# nv-h5b.net
KiCad netlist of a schematic drawn in EAGLE
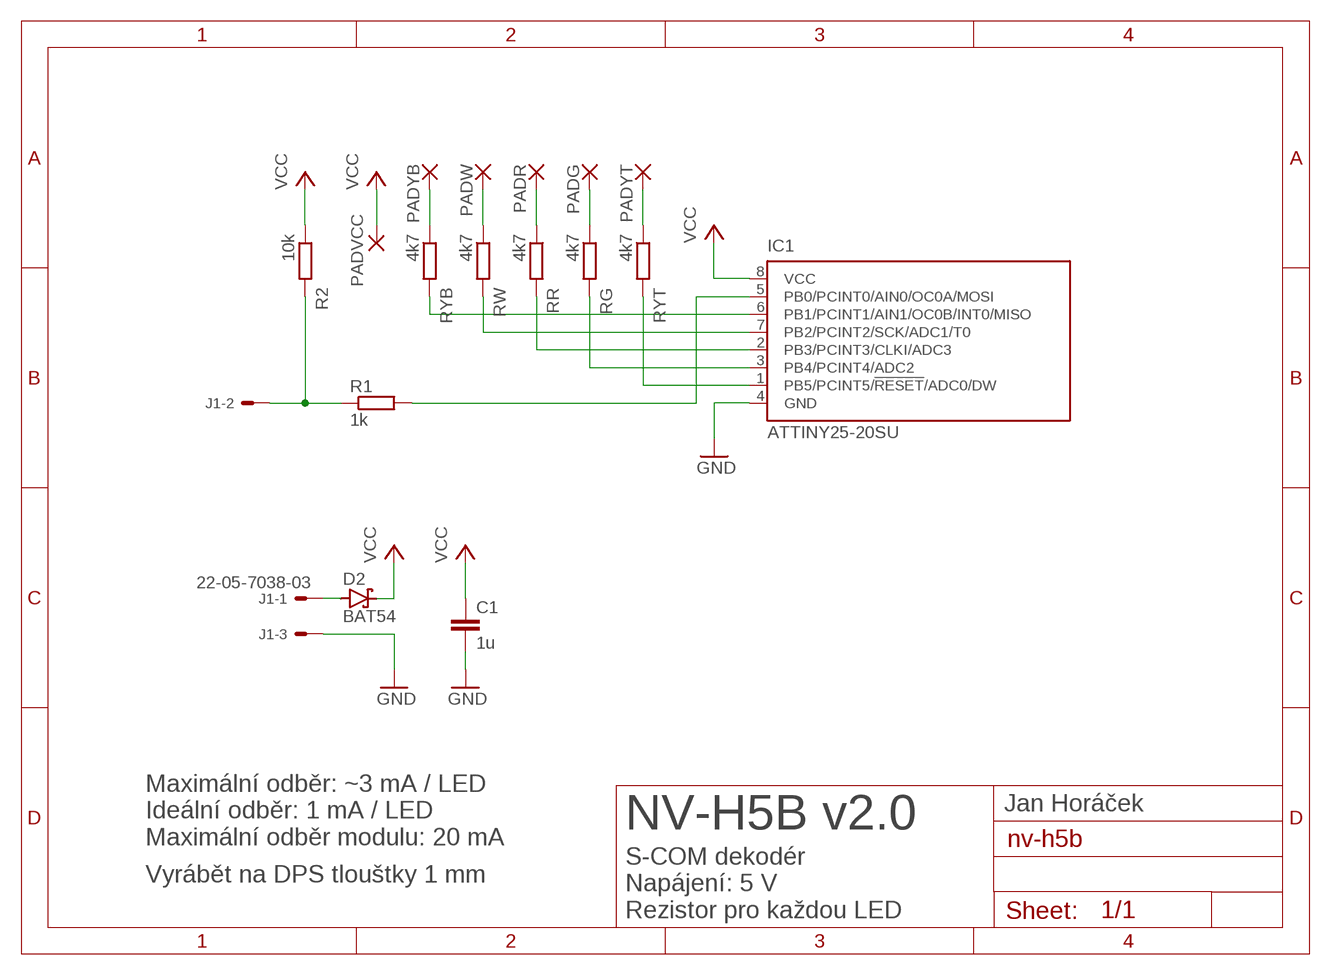
[diagram p0: schematic, sheet 1]

(export (version "E")
  (design (tool "Eeschema 10.0.6"))
  (components
    (comp (ref "C1")
      (value "1u")
      (footprint "eagle-import:C0805")
      (libsource (lib "eagle-import") (part "C-EUC0805"))
    )
    (comp (ref "D2")
      (value "BAT54")
      (footprint "eagle-import:SOT23")
      (libsource (lib "eagle-import") (part "BAT54"))
    )
    (comp (ref "IC1")
      (value "ATTINY25-20SU")
      (footprint "eagle-import:8S1")
      (fields (field (name "MPN") "ATTINY13-20SSU"))
      (libsource (lib "eagle-import") (part "TINY13SSU-20"))
    )
    (comp (ref "J1")
      (value "22-05-7038-03")
      (footprint "eagle-import:7395-03")
      (fields (field (name "MF") "MOLEX"))
      (libsource (lib "eagle-import") (part "22-?-0305-7038"))
    )
    (comp (ref "PADG")
      (value "SMD3")
      (footprint "eagle-import:SMD1,778-5,08")
      (libsource (lib "eagle-import") (part "SMD3"))
    )
    (comp (ref "PADR")
      (value "SMD3")
      (footprint "eagle-import:SMD1,778-5,08")
      (libsource (lib "eagle-import") (part "SMD3"))
    )
    (comp (ref "PADVCC")
      (value "SMD3")
      (footprint "eagle-import:SMD1,778-5,08")
      (libsource (lib "eagle-import") (part "SMD3"))
    )
    (comp (ref "PADW")
      (value "SMD3")
      (footprint "eagle-import:SMD1,778-5,08")
      (libsource (lib "eagle-import") (part "SMD3"))
    )
    (comp (ref "PADYB")
      (value "SMD3")
      (footprint "eagle-import:SMD1,778-5,08")
      (libsource (lib "eagle-import") (part "SMD3"))
    )
    (comp (ref "PADYT")
      (value "SMD3")
      (footprint "eagle-import:SMD1,778-5,08")
      (libsource (lib "eagle-import") (part "SMD3"))
    )
    (comp (ref "R1")
      (value "1k")
      (footprint "eagle-import:R0805")
      (libsource (lib "eagle-import") (part "R-EU_R0805"))
    )
    (comp (ref "R2")
      (value "10k")
      (footprint "eagle-import:R0805")
      (libsource (lib "eagle-import") (part "R-EU_R0805"))
    )
    (comp (ref "RG")
      (value "4k7")
      (footprint "eagle-import:R0805")
      (libsource (lib "eagle-import") (part "R-EU_R0805"))
    )
    (comp (ref "RR")
      (value "4k7")
      (footprint "eagle-import:R0805")
      (libsource (lib "eagle-import") (part "R-EU_R0805"))
    )
    (comp (ref "RW")
      (value "4k7")
      (footprint "eagle-import:R0805")
      (libsource (lib "eagle-import") (part "R-EU_R0805"))
    )
    (comp (ref "RYB")
      (value "4k7")
      (footprint "eagle-import:R0805")
      (libsource (lib "eagle-import") (part "R-EU_R0805"))
    )
    (comp (ref "RYT")
      (value "4k7")
      (footprint "eagle-import:R0805")
      (libsource (lib "eagle-import") (part "R-EU_R0805"))
    )
  )
  (nets
    (net (code "1") (name "GND") (class "Default")
      (node (ref "C1") (pin "2") (pinfunction "2_2") (pintype "passive"))
      (node (ref "IC1") (pin "4") (pinfunction "GND_4") (pintype "power_in"))
      (node (ref "J1") (pin "3") (pinfunction "S_3") (pintype "passive"))
    )
    (net (code "2") (name "Net-(D2-A)") (class "Default")
      (node (ref "D2") (pin "1") (pinfunction "A_1") (pintype "passive"))
      (node (ref "J1") (pin "1") (pinfunction "S_1") (pintype "passive"))
    )
    (net (code "3") (name "Net-(IC1-PB0{slash}PCINT0{slash}AIN0{slash}OC0A{slash}MOSI)") (class "Default")
      (node (ref "IC1") (pin "5") (pinfunction "PB0/PCINT0/AIN0/OC0A/MOSI_5") (pintype "bidirectional"))
      (node (ref "R1") (pin "2") (pinfunction "2_2") (pintype "passive"))
    )
    (net (code "4") (name "Net-(IC1-PB1{slash}PCINT1{slash}AIN1{slash}OC0B{slash}INT0{slash}MISO)") (class "Default")
      (node (ref "IC1") (pin "6") (pinfunction "PB1/PCINT1/AIN1/OC0B/INT0/MISO_6") (pintype "bidirectional"))
      (node (ref "RYB") (pin "2") (pinfunction "2_2") (pintype "passive"))
    )
    (net (code "5") (name "Net-(IC1-PB2{slash}PCINT2{slash}SCK{slash}ADC1{slash}T0)") (class "Default")
      (node (ref "IC1") (pin "7") (pinfunction "PB2/PCINT2/SCK/ADC1/T0_7") (pintype "bidirectional"))
      (node (ref "RW") (pin "2") (pinfunction "2_2") (pintype "passive"))
    )
    (net (code "6") (name "Net-(IC1-PB3{slash}PCINT3{slash}CLKI{slash}ADC3)") (class "Default")
      (node (ref "IC1") (pin "2") (pinfunction "PB3/PCINT3/CLKI/ADC3_2") (pintype "bidirectional"))
      (node (ref "RR") (pin "2") (pinfunction "2_2") (pintype "passive"))
    )
    (net (code "7") (name "Net-(IC1-PB4{slash}PCINT4{slash}ADC2)") (class "Default")
      (node (ref "IC1") (pin "3") (pinfunction "PB4/PCINT4/ADC2_3") (pintype "bidirectional"))
      (node (ref "RG") (pin "2") (pinfunction "2_2") (pintype "passive"))
    )
    (net (code "8") (name "Net-(IC1-PB5{slash}PCINT5{slash}~{RESET}{slash}ADC0{slash}DW)") (class "Default")
      (node (ref "IC1") (pin "1") (pinfunction "PB5/PCINT5/~{RESET}/ADC0/DW_1") (pintype "bidirectional"))
      (node (ref "RYT") (pin "2") (pinfunction "2_2") (pintype "passive"))
    )
    (net (code "9") (name "Net-(J1B-S)") (class "Default")
      (node (ref "J1") (pin "2") (pinfunction "S_2") (pintype "passive"))
      (node (ref "R1") (pin "1") (pinfunction "1_1") (pintype "passive"))
      (node (ref "R2") (pin "2") (pinfunction "2_2") (pintype "passive"))
    )
    (net (code "10") (name "Net-(PADG-P)") (class "Default")
      (node (ref "PADG") (pin "1") (pinfunction "P_1") (pintype "passive"))
      (node (ref "RG") (pin "1") (pinfunction "1_1") (pintype "passive"))
    )
    (net (code "11") (name "Net-(PADR-P)") (class "Default")
      (node (ref "PADR") (pin "1") (pinfunction "P_1") (pintype "passive"))
      (node (ref "RR") (pin "1") (pinfunction "1_1") (pintype "passive"))
    )
    (net (code "12") (name "Net-(PADW-P)") (class "Default")
      (node (ref "PADW") (pin "1") (pinfunction "P_1") (pintype "passive"))
      (node (ref "RW") (pin "1") (pinfunction "1_1") (pintype "passive"))
    )
    (net (code "13") (name "Net-(PADYB-P)") (class "Default")
      (node (ref "PADYB") (pin "1") (pinfunction "P_1") (pintype "passive"))
      (node (ref "RYB") (pin "1") (pinfunction "1_1") (pintype "passive"))
    )
    (net (code "14") (name "Net-(PADYT-P)") (class "Default")
      (node (ref "PADYT") (pin "1") (pinfunction "P_1") (pintype "passive"))
      (node (ref "RYT") (pin "1") (pinfunction "1_1") (pintype "passive"))
    )
    (net (code "15") (name "VCC") (class "Default")
      (node (ref "C1") (pin "1") (pinfunction "1_1") (pintype "passive"))
      (node (ref "D2") (pin "3") (pinfunction "C_3") (pintype "passive"))
      (node (ref "IC1") (pin "8") (pinfunction "VCC_8") (pintype "power_in"))
      (node (ref "PADVCC") (pin "1") (pinfunction "P_1") (pintype "passive"))
      (node (ref "R2") (pin "1") (pinfunction "1_1") (pintype "passive"))
    )
  )
)
